# jn5169_blk.net
KiCad netlist of a schematic drawn in Altium Designer
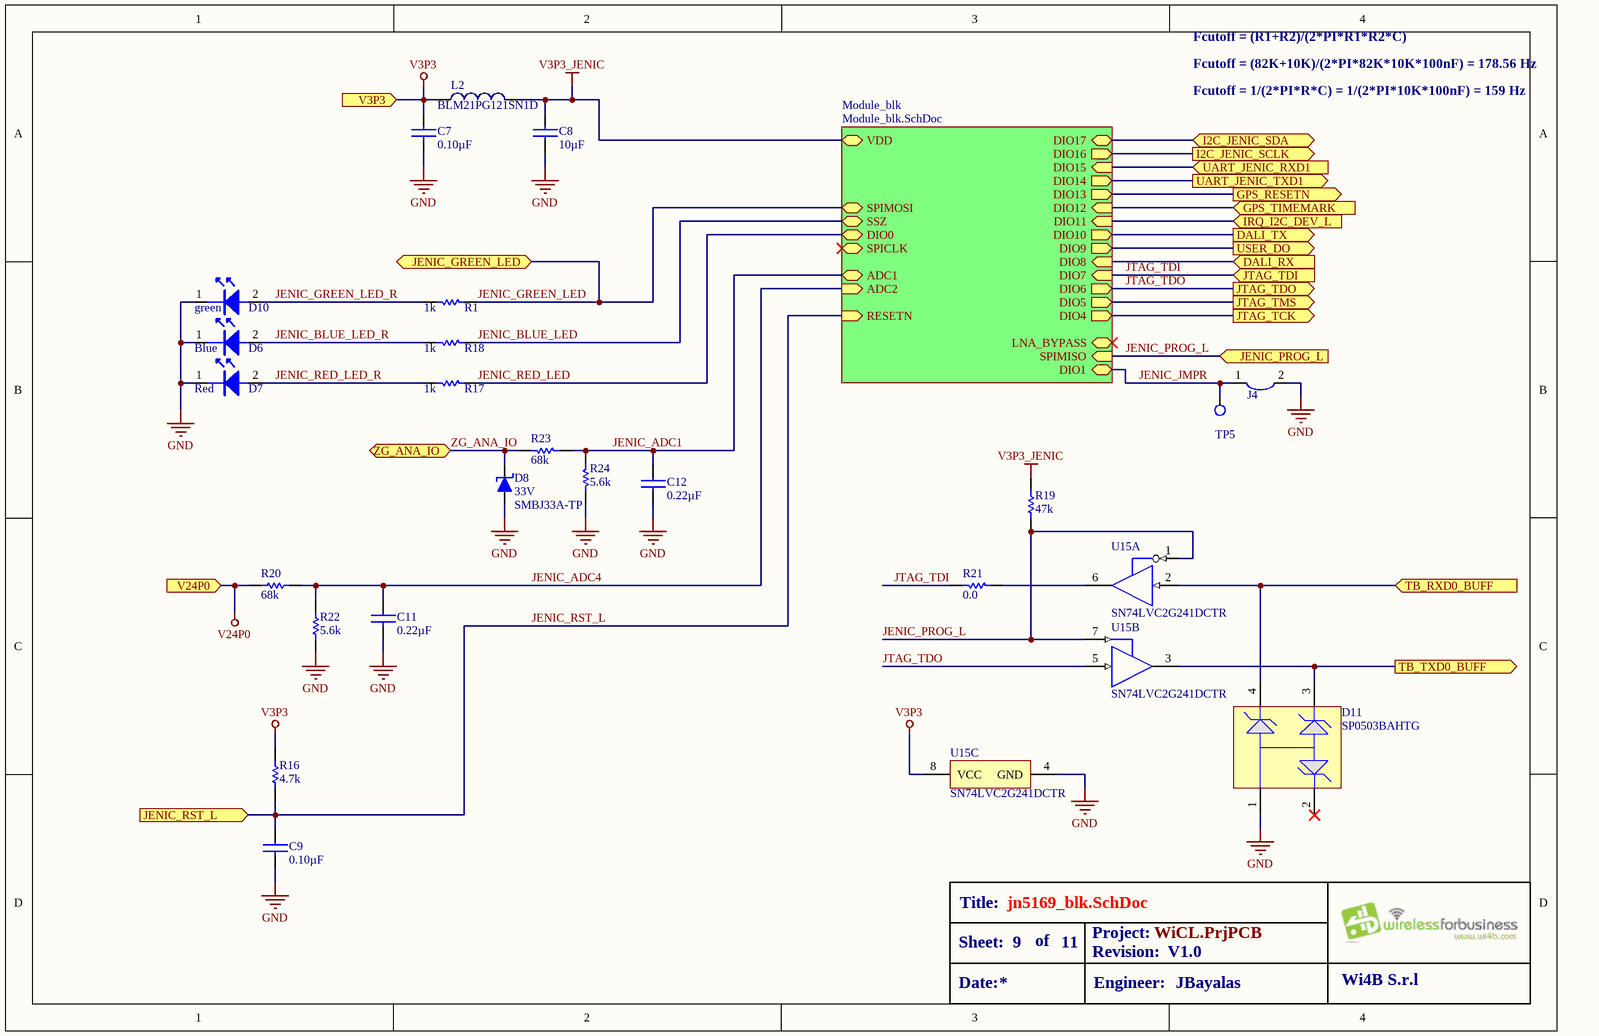
[diagram p0: jn5169_blk.SchDoc]

(export (version "E")
  (design (tool "Eeschema 10.0.6"))
  (components
    (comp (ref "C7")
      (value "0.10µF")
      (footprint "C0402")
      (description "CAP CER 0.1UF 50V X7R 0402")
      (fields (field (name "MPN") "GRM155R71H104ME14D"))
      (libsource (lib "Capacitor") (part "GRM155R71H104ME14D"))
    )
    (comp (ref "C8")
      (value "10µF")
      (footprint "C1206")
      (description "CAP CER 10UF 16V X7R 1206")
      (fields (field (name "MPN") "GRM31CR71C106KAC7L"))
      (libsource (lib "Capacitor") (part "GRM31CR71C106KAC7L"))
    )
    (comp (ref "C9")
      (value "0.10µF")
      (footprint "C0402")
      (description "CAP CER 0.1UF 50V X7R 0402")
      (fields (field (name "MPN") "GRM155R71H104ME14D"))
      (libsource (lib "Capacitor") (part "GRM155R71H104ME14D"))
    )
    (comp (ref "C11")
      (value "0.22µF")
      (footprint "C0603")
      (description "CAP CER 0.22UF 50V X7R 0603")
      (fields (field (name "MPN") "GCM188R71H224KA64D"))
      (libsource (lib "Capacitor") (part "GCM188R71H224KA64D"))
    )
    (comp (ref "C12")
      (value "0.22µF")
      (footprint "C0603")
      (description "CAP CER 0.22UF 50V X7R 0603")
      (fields (field (name "MPN") "GCM188R71H224KA64D"))
      (libsource (lib "wiLamp_st") (part "GCM188R71H224KA64D"))
    )
    (comp (ref "D6")
      (value "Blue")
      (footprint "LED0402(BLUE)")
      (description "LED BLUE 0402 SMD")
      (fields (field (name "MPN") "VLMB1500-GS08"))
      (libsource (lib "Diode") (part "VLMB1500-GS08"))
    )
    (comp (ref "D7")
      (value "Red")
      (footprint "LED0402(RED)")
      (description "LED RED 0402 SMD")
      (fields (field (name "MPN") "VLMS1500-GS08"))
      (libsource (lib "Diode") (part "VLMS1500-GS08"))
    )
    (comp (ref "D8")
      (value "SMBJ33A-TP")
      (footprint "DO-214AA, SMB")
      (description "TVS DIODE 33VWM 53.3VC SMB")
      (fields (field (name "RATING") "33V") (field (name "MPN") "SMBJ33A-TP"))
      (libsource (lib "wilamp_st") (part "SMBJ33A-TP"))
    )
    (comp (ref "D10")
      (value "green")
      (footprint "LED0402(GREEN)")
      (description "LED GREEN CLEAR CHIP SMD")
      (fields (field (name "MPN") "XZVG68W-2"))
      (libsource (lib "Diode") (part "XZVG68W-2"))
    )
    (comp (ref "D11")
      (value "SP0503BAHTG")
      (footprint "LFUS-SOT143-4_V")
      (description "TVS Diode Array, 30 pF, 30 KV, -40 to 85 degC, 4-Pin SOT143, RoHS, Tape and Reel")
      (fields (field (name "MANUFACTURER") "Littelfuse"))
      (libsource (lib "Altium Content Vault") (part "LFUS-SP0503BAHTG-SOT143-4"))
    )
    (comp (ref "J4")
      (value "0603 Jumper")
      (footprint "0603 Jumper")
      (libsource (lib "Connector") (part "0603 Jumper"))
    )
    (comp (ref "L2")
      (value "BLM21PG121SN1D")
      (footprint "0805 INDUCTOR")
      (description "FERRITE CHIP 120 OHM 0805")
      (fields (field (name "MPN") "BLM21PG121SN1D"))
      (libsource (lib "Inductor") (part "BLM21PG121SN1D"))
    )
    (comp (ref "R1")
      (value "1k")
      (footprint "R0402")
      (description "RES SMD 1K OHM 1% 1/10W 0402")
      (fields (field (name "MPN") "MCS04020C1001FE000"))
      (libsource (lib "Res") (part "MCS04020C1001FE000"))
    )
    (comp (ref "R16")
      (value "4.7k")
      (footprint "R0402")
      (description "RES SMD 4.7K OHM 1% 1/10W 0402")
      (fields (field (name "MPN") "MCS04020C4701FE000"))
      (libsource (lib "Res") (part "MCS04020C4701FE000"))
    )
    (comp (ref "R17")
      (value "1k")
      (footprint "R0402")
      (description "RES SMD 1K OHM 1% 1/10W 0402")
      (fields (field (name "MPN") "MCS04020C1001FE000"))
      (libsource (lib "Res") (part "MCS04020C1001FE000"))
    )
    (comp (ref "R18")
      (value "1k")
      (footprint "R0402")
      (description "RES SMD 1K OHM 1% 1/10W 0402")
      (fields (field (name "MPN") "MCS04020C1001FE000"))
      (libsource (lib "Res") (part "MCS04020C1001FE000"))
    )
    (comp (ref "R19")
      (value "47k")
      (footprint "R0402")
      (description "RES SMD 47K OHM 1% 1/16W 0402")
      (fields (field (name "MPN") "RC0402FR-0747KL"))
      (libsource (lib "Res") (part "RC0402FR-0747KL"))
    )
    (comp (ref "R20")
      (value "68k")
      (footprint "R0603")
      (description "RES SMD 68K OHM 0.1% 1/10W 0603")
      (fields (field (name "MPN") "ERA-3AEB683V"))
      (libsource (lib "Res") (part "ERA-3AEB683V"))
    )
    (comp (ref "R21")
      (value "0.0")
      (footprint "R0402")
      (description "RES SMD 0.0OHM JUMPER 1/16W 0402")
      (fields (field (name "MPN") "CRCW04020000Z0ED"))
      (libsource (lib "Res") (part "CRCW04020000Z0ED"))
    )
    (comp (ref "R22")
      (value "5.6k")
      (footprint "R0603")
      (description "RES SMD 5.6K OHM 0.1% 1/10W 0603")
      (fields (field (name "MPN") "ERA-3AEB562V"))
      (libsource (lib "Res") (part "ERA-3AEB562V"))
    )
    (comp (ref "R23")
      (value "68k")
      (footprint "R0603")
      (description "RES SMD 68K OHM 0.1% 1/10W 0603")
      (fields (field (name "MPN") "ERA-3AEB683V"))
      (libsource (lib "Res") (part "ERA-3AEB683V"))
    )
    (comp (ref "R24")
      (value "5.6k")
      (footprint "R0603")
      (description "RES SMD 5.6K OHM 0.1% 1/10W 0603")
      (fields (field (name "MPN") "ERA-3AEB562V"))
      (libsource (lib "Res") (part "ERA-3AEB562V"))
    )
    (comp (ref "TP5")
      (value "Test Point_2mm")
      (footprint "Test Point 2mm")
      (description "Test Point 2mm")
      (libsource (lib "Miscellaneous") (part "Test Point_2mm"))
    )
    (comp (ref "U15")
      (value "SN74LVC2G241DCTR")
      (footprint "DCT0008A_L")
      (description "Dual Buffer/Driver With 3-State Outputs, DCT0008A, LARGE T&R")
      (fields
        (field (name "GENERIC PART NUMBER") "SN74LVC2G241")
        (field (name "MANUFACTURER") "Texas Instruments")
      )
      (libsource (lib "") (part "TI-SN74XXX2G241-8_1"))
    )
  )
  (nets
    (net (code "8") (name "/JENIC_ADC1") (class "Default")
      (node (ref "C12") (pin "1") (pinfunction "1_1") (pintype "passive"))
      (node (ref "R23") (pin "2") (pinfunction "2_2") (pintype "passive"))
      (node (ref "R24") (pin "2") (pinfunction "2_2") (pintype "passive"))
    )
    (net (code "9") (name "/JENIC_ADC4") (class "Default")
      (node (ref "C11") (pin "1") (pinfunction "1_1") (pintype "passive"))
      (node (ref "R20") (pin "1") (pinfunction "1_1") (pintype "passive"))
      (node (ref "R22") (pin "2") (pinfunction "2_2") (pintype "passive"))
    )
    (net (code "10") (name "/JENIC_BLUE_LED") (class "Default")
      (node (ref "R18") (pin "2") (pinfunction "2_2") (pintype "passive"))
    )
    (net (code "11") (name "/JENIC_BLUE_LED_R") (class "Default")
      (node (ref "D6") (pin "2") (pinfunction "2_2") (pintype "passive"))
      (node (ref "R18") (pin "1") (pinfunction "1_1") (pintype "passive"))
    )
    (net (code "12") (name "/JENIC_GREEN_LED") (class "Default")
      (node (ref "R1") (pin "2") (pinfunction "2_2") (pintype "passive"))
    )
    (net (code "13") (name "/JENIC_GREEN_LED_R") (class "Default")
      (node (ref "D10") (pin "2") (pinfunction "2_2") (pintype "passive"))
      (node (ref "R1") (pin "1") (pinfunction "1_1") (pintype "passive"))
    )
    (net (code "14") (name "/JENIC_JMPR") (class "Default")
      (node (ref "J4") (pin "1") (pinfunction "1_1") (pintype "passive"))
      (node (ref "TP5") (pin "1") (pinfunction "1_1") (pintype "passive"))
    )
    (net (code "15") (name "/JENIC_PROG_L") (class "Default")
      (node (ref "R19") (pin "1") (pinfunction "1_1") (pintype "passive"))
      (node (ref "U15") (pin "1") (pinfunction "1~{OE}_1") (pintype "input"))
      (node (ref "U15") (pin "7") (pinfunction "2OE_7") (pintype "input"))
    )
    (net (code "16") (name "/JENIC_RED_LED") (class "Default")
      (node (ref "R17") (pin "2") (pinfunction "2_2") (pintype "passive"))
    )
    (net (code "17") (name "/JENIC_RED_LED_R") (class "Default")
      (node (ref "D7") (pin "2") (pinfunction "2_2") (pintype "passive"))
      (node (ref "R17") (pin "1") (pinfunction "1_1") (pintype "passive"))
    )
    (net (code "18") (name "/JENIC_RST_L") (class "Default")
      (node (ref "C9") (pin "1") (pinfunction "1_1") (pintype "passive"))
      (node (ref "R16") (pin "1") (pinfunction "1_1") (pintype "passive"))
    )
    (net (code "20") (name "/JTAG_TDI") (class "Default")
      (node (ref "R21") (pin "1") (pinfunction "1_1") (pintype "passive"))
    )
    (net (code "21") (name "/JTAG_TDO") (class "Default")
      (node (ref "U15") (pin "5") (pinfunction "2A_5") (pintype "input"))
    )
    (net (code "25") (name "/TB_RXD0_BUFF") (class "Default")
      (node (ref "D11") (pin "4") (pinfunction "4_4") (pintype "passive"))
      (node (ref "U15") (pin "2") (pinfunction "1A_2") (pintype "input"))
    )
    (net (code "26") (name "/TB_TXD0_BUFF") (class "Default")
      (node (ref "D11") (pin "3") (pinfunction "3_3") (pintype "passive"))
      (node (ref "U15") (pin "3") (pinfunction "2Y_3") (pintype "tri_state"))
    )
    (net (code "30") (name "/ZG_ANA_IO") (class "Default")
      (node (ref "D8") (pin "1") (pinfunction "K_1") (pintype "passive"))
      (node (ref "R23") (pin "1") (pinfunction "1_1") (pintype "passive"))
    )
    (net (code "31") (name "GND") (class "Default")
      (node (ref "C11") (pin "2") (pinfunction "2_2") (pintype "passive"))
      (node (ref "C12") (pin "2") (pinfunction "2_2") (pintype "passive"))
      (node (ref "C7") (pin "2") (pinfunction "2_2") (pintype "passive"))
      (node (ref "C8") (pin "2") (pinfunction "2_2") (pintype "passive"))
      (node (ref "C9") (pin "2") (pinfunction "2_2") (pintype "passive"))
      (node (ref "D10") (pin "1") (pinfunction "1_1") (pintype "passive"))
      (node (ref "D11") (pin "1") (pinfunction "1_1") (pintype "passive"))
      (node (ref "D6") (pin "1") (pinfunction "1_1") (pintype "passive"))
      (node (ref "D7") (pin "1") (pinfunction "1_1") (pintype "passive"))
      (node (ref "D8") (pin "2") (pinfunction "A_2") (pintype "passive"))
      (node (ref "J4") (pin "2") (pinfunction "2_2") (pintype "passive"))
      (node (ref "R22") (pin "1") (pinfunction "1_1") (pintype "passive"))
      (node (ref "R24") (pin "1") (pinfunction "1_1") (pintype "passive"))
      (node (ref "U15") (pin "4") (pinfunction "GND_4") (pintype "power_in"))
    )
    (net (code "32") (name "Net-(U15A-1Y)") (class "Default")
      (node (ref "R21") (pin "2") (pinfunction "2_2") (pintype "passive"))
      (node (ref "U15") (pin "6") (pinfunction "1Y_6") (pintype "tri_state"))
    )
    (net (code "33") (name "V3P3") (class "Default")
      (node (ref "C7") (pin "1") (pinfunction "1_1") (pintype "passive"))
      (node (ref "L2") (pin "2") (pinfunction "2_2") (pintype "passive"))
      (node (ref "R16") (pin "2") (pinfunction "2_2") (pintype "passive"))
      (node (ref "U15") (pin "8") (pinfunction "VCC_8") (pintype "power_in"))
    )
    (net (code "34") (name "V3P3_JENIC") (class "Default")
      (node (ref "C8") (pin "1") (pinfunction "1_1") (pintype "passive"))
      (node (ref "L2") (pin "1") (pinfunction "1_1") (pintype "passive"))
      (node (ref "R19") (pin "2") (pinfunction "2_2") (pintype "passive"))
    )
    (net (code "35") (name "V24P0") (class "Default")
      (node (ref "R20") (pin "2") (pinfunction "2_2") (pintype "passive"))
    )
    (net (code "36") (name "unconnected-(D11-Pad2)") (class "Default")
      (node (ref "D11") (pin "2") (pinfunction "2_2") (pintype "passive+no_connect"))
    )
  )
)
